# ind3v3.net
KiCad netlist of a schematic drawn in Altium Designer
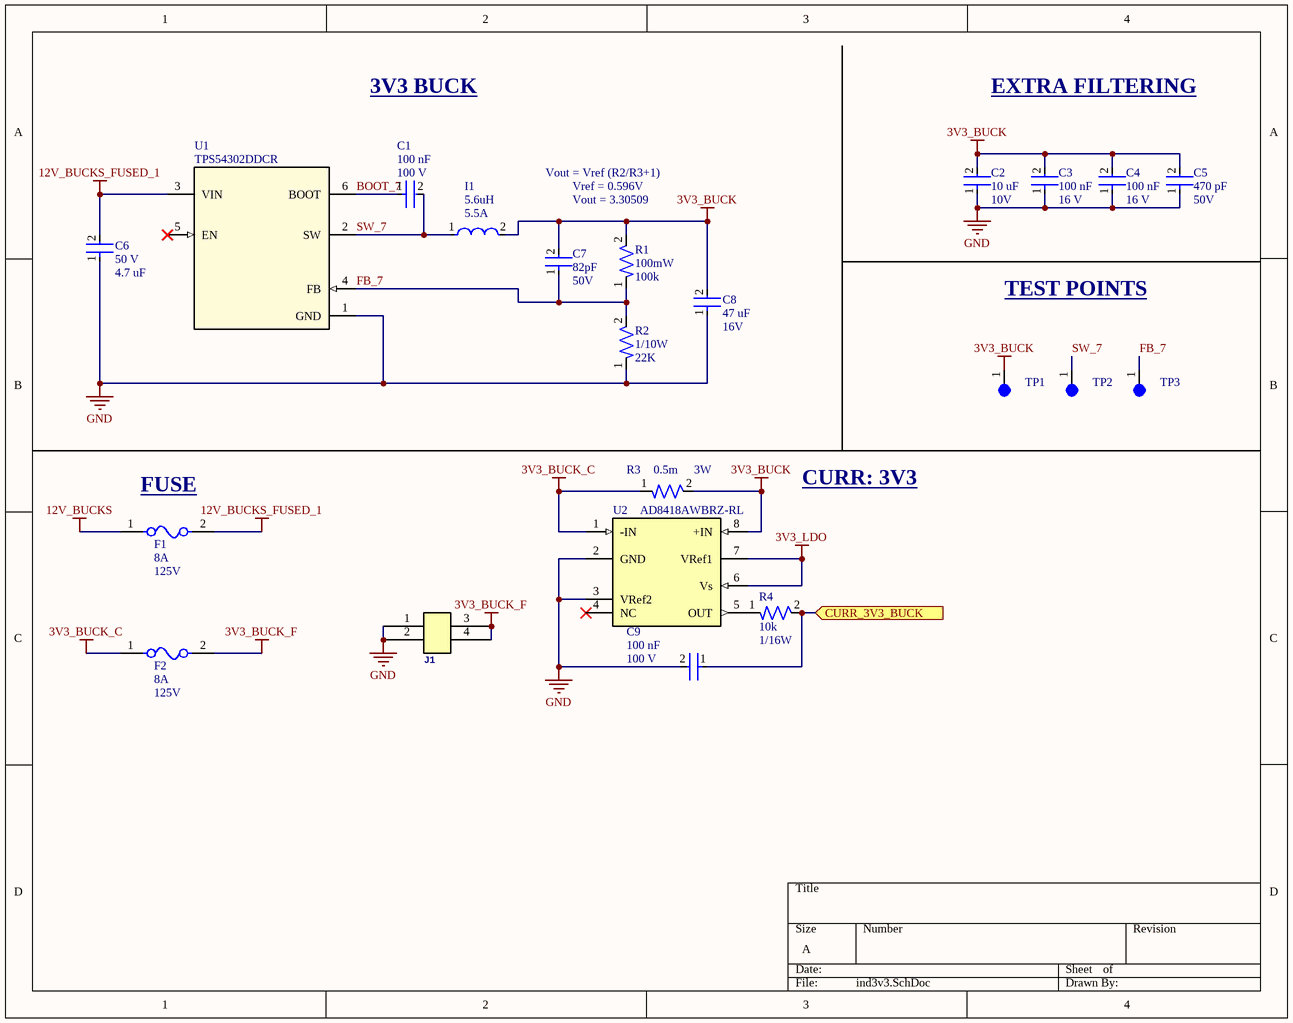
[diagram p0: ind3v3.SchDoc]

(export (version "E")
  (design (tool "Eeschema 10.0.6"))
  (components
    (comp (ref "C1")
      (value "CC0603KRX7R0BB104")
      (footprint "CAP-0603")
      (description "CAP CER 0.1UF 100V X7R 0603")
      (fields (field (name "CAPACITANCE") "100 nF") (field (name "VOLTAGE") "100 V"))
      (libsource (lib "JLC_25") (part "CAP-100N-0001"))
    )
    (comp (ref "C2")
      (value "CC0603KRX5R6BB106")
      (footprint "CAP-0603")
      (description "CAP CER 10UF 10V X5R 0603")
      (fields (field (name "VOLTAGE") "10V") (field (name "CAPACITANCE") "10 uF"))
      (libsource (lib "JLC_25") (part "CAP-10U-0001"))
    )
    (comp (ref "C3")
      (value "CC0402KRX7R7BB104")
      (footprint "CAP-0402")
      (description "CAP CER 0.1UF 16V X7R 0402")
      (fields (field (name "VOLTAGE RATING") "16 V") (field (name "CAPACITANCE") "100 nF"))
      (libsource (lib "JLC_25") (part "CAP-0.1U-0001"))
    )
    (comp (ref "C4")
      (value "CC0402KRX7R7BB104")
      (footprint "CAP-0402")
      (description "CAP CER 0.1UF 16V X7R 0402")
      (fields (field (name "VOLTAGE RATING") "16 V") (field (name "CAPACITANCE") "100 nF"))
      (libsource (lib "JLC_25") (part "CAP-0.1U-0001"))
    )
    (comp (ref "C5")
      (value "CC0805JRNPO9BN471")
      (footprint "CAP-0805")
      (description "CAP CER 470PF 50V C0G/NPO 0805")
      (fields (field (name "VOLTAGE") "50V") (field (name "CAPACITANCE") "470 pF"))
      (libsource (lib "JLC_25") (part "CAP-470P-0001"))
    )
    (comp (ref "C6")
      (value "CC0805KKX5R9BB475")
      (footprint "CAP-0805")
      (description "CAP CER 4.7UF 50V X5R 0805")
      (fields (field (name "VOLTAGE") "50 V") (field (name "CAPACITANCE") "4.7 uF"))
      (libsource (lib "JLC_25") (part "CAP-4.7U-0002"))
    )
    (comp (ref "C7")
      (value "CC0805JRNPO9BN820")
      (footprint "CAP-0805")
      (description "82 pF ±5% 50V Ceramic Capacitor C0G, NP0 0805 (2012 Metric)")
      (fields (field (name "VOLTAGE") "50V") (field (name "CAPACITANCE") "82pF"))
      (libsource (lib "JLC_25") (part "CAP-82P-0001"))
    )
    (comp (ref "C8")
      (value "GRM32ER61C476KE15L")
      (footprint "CAP-1210")
      (description "CAP CER 47UF 16V X5R 1210")
      (fields (field (name "CAPACITANCE") "47 uF") (field (name "VOLTAGE") "16V"))
      (libsource (lib "JLC_25") (part "CAP-47U-0002"))
    )
    (comp (ref "C9")
      (value "CC0603KRX7R0BB104")
      (footprint "CAP-0603")
      (description "CAP CER 0.1UF 100V X7R 0603")
      (fields (field (name "CAPACITANCE") "100 nF") (field (name "VOLTAGE") "100 V"))
      (libsource (lib "JLC_25") (part "CAP-100N-0001"))
    )
    (comp (ref "F1")
      (value "01550900M")
      (footprint "FUSE-0001")
      (description "FUSE BLOK CARTRIDGE 125V 10A SMD")
      (fields (field (name "FUSE CURRENT") "8A") (field (name "VOLTAGE RATING") "125V"))
      (libsource (lib "JLC_25") (part "FUSE-0001"))
    )
    (comp (ref "F2")
      (value "01550900M")
      (footprint "FUSE-0001")
      (description "FUSE BLOK CARTRIDGE 125V 10A SMD")
      (fields (field (name "FUSE CURRENT") "8A") (field (name "VOLTAGE RATING") "125V"))
      (libsource (lib "JLC_25") (part "FUSE-0001"))
    )
    (comp (ref "I1")
      (value "SRP6540-5R6M")
      (footprint "IND_SRP6540-5R6M")
      (description "FIXED IND 5.6UH 5.5A 38 MOHM SMD")
      (fields (field (name "SATURATION CURRENT") "5.5A") (field (name "INDUCTANCE") "5.6uH"))
      (libsource (lib "JLC_25") (part "IND-5.6U-0002"))
    )
    (comp (ref "J1")
      (value "Molex 43045-0412")
      (footprint "CONN-4POS-0002")
      (description "CONN HEADER VERT 4POS 3MM")
      (libsource (lib "JLC_25") (part "CONN-4POS-0002"))
    )
    (comp (ref "R1")
      (value "RC0603FR-07100KL")
      (footprint "RES-0603")
      (description "RES SMD 100K OHM 1% 1/10W 0603")
      (fields
        (field (name "TOLERANCE") "1%")
        (field (name "POWER") "100mW")
        (field (name "RESISTANCE") "100k")
      )
      (libsource (lib "JLC_25") (part "RES-100k-0001"))
    )
    (comp (ref "R2")
      (value "RC0603FR-0722KL")
      (footprint "RES-0603")
      (description "22 kOhms ±1% 0.1W, 1/10W Chip Resistor 0603 (1608 Metric) Moisture Resistant Thick Film")
      (fields (field (name "POWER") "1/10W") (field (name "RESISTANCE") "22K"))
      (libsource (lib "JLC_25") (part "RES-22k-0001"))
    )
    (comp (ref "R3")
      (value "CSNL2512FTL500")
      (footprint "RES-2512")
      (description "2512 Chip Resistor - Surface Mount ROHS")
      (fields (field (name "TOLERANCE") "1%") (field (name "POWER") "3W") (field (name "RESISTANCE") "0.5m"))
      (libsource (lib "JLC_25") (part "RES-0.5m-0001"))
    )
    (comp (ref "R4")
      (value "RC0402FR-0710KL")
      (footprint "RES-0402")
      (description "RES 10K OHM 1% 1/16W 0402")
      (fields
        (field (name "TOLERANCE") "1%")
        (field (name "RESISTANCE") "10k")
        (field (name "POWER") "1/16W")
      )
      (libsource (lib "JLC_25") (part "RES-10k-0001"))
    )
    (comp (ref "TP1")
      (value "5003")
      (footprint "TEST-POINT-0001")
      (description "Oranange PC Test Point, Miniature Phoisphor Bronze Silver Plating Through Hole Mounting Type")
      (libsource (lib "*") (part "TEST-POINT-0001"))
    )
    (comp (ref "TP2")
      (value "5003")
      (footprint "TEST-POINT-0001")
      (description "Oranange PC Test Point, Miniature Phoisphor Bronze Silver Plating Through Hole Mounting Type")
      (libsource (lib "*") (part "TEST-POINT-0001"))
    )
    (comp (ref "TP3")
      (value "5003")
      (footprint "TEST-POINT-0001")
      (description "Oranange PC Test Point, Miniature Phoisphor Bronze Silver Plating Through Hole Mounting Type")
      (libsource (lib "*") (part "TEST-POINT-0001"))
    )
    (comp (ref "U1")
      (value "TPS54302DDCR")
      (footprint "IC-SOT-23-6")
      (description "IC REG BUCK ADJ 3A SOT23")
      (libsource (lib "JLC_25") (part "IC-BUCK-0004"))
    )
    (comp (ref "U2")
      (value "AD8418AWBRZ-RL")
      (footprint "IC-CURR")
      (description "Current Sense Amplifier 1 Circuit 8-MSOP")
      (libsource (lib "JLC_25") (part "IC-CURR-0001"))
    )
  )
  (nets
    (net (code "1") (name "/BOOT_7") (class "Default")
      (node (ref "C1") (pin "1") (pinfunction "1_1") (pintype "passive"))
      (node (ref "U1") (pin "6") (pinfunction "BOOT_6") (pintype "power_in"))
    )
    (net (code "2") (name "/CURR_3V3_BUCK") (class "Default")
      (node (ref "C9") (pin "1") (pinfunction "1_1") (pintype "passive"))
      (node (ref "R4") (pin "2") (pinfunction "2_2") (pintype "passive"))
    )
    (net (code "3") (name "/FB_7") (class "Default")
      (node (ref "C7") (pin "1") (pinfunction "1_1") (pintype "passive"))
      (node (ref "R1") (pin "1") (pinfunction "1_1") (pintype "passive"))
      (node (ref "R2") (pin "2") (pinfunction "2_2") (pintype "passive"))
      (node (ref "TP3") (pin "1") (pinfunction "0_1") (pintype "passive"))
      (node (ref "U1") (pin "4") (pinfunction "FB_4") (pintype "input"))
    )
    (net (code "4") (name "/SW_7") (class "Default")
      (node (ref "C1") (pin "2") (pinfunction "2_2") (pintype "passive"))
      (node (ref "I1") (pin "1") (pinfunction "1_1") (pintype "passive"))
      (node (ref "TP2") (pin "1") (pinfunction "0_1") (pintype "passive"))
      (node (ref "U1") (pin "2") (pinfunction "SW_2") (pintype "power_in"))
    )
    (net (code "5") (name "3V3_BUCK") (class "Default")
      (node (ref "C2") (pin "2") (pinfunction "2_2") (pintype "passive"))
      (node (ref "C3") (pin "2") (pinfunction "2_2") (pintype "passive"))
      (node (ref "C4") (pin "2") (pinfunction "2_2") (pintype "passive"))
      (node (ref "C5") (pin "2") (pinfunction "2_2") (pintype "passive"))
      (node (ref "C7") (pin "2") (pinfunction "2_2") (pintype "passive"))
      (node (ref "C8") (pin "2") (pinfunction "2_2") (pintype "passive"))
      (node (ref "I1") (pin "2") (pinfunction "2_2") (pintype "passive"))
      (node (ref "R1") (pin "2") (pinfunction "2_2") (pintype "passive"))
      (node (ref "R3") (pin "2") (pinfunction "2_2") (pintype "passive"))
      (node (ref "TP1") (pin "1") (pinfunction "0_1") (pintype "passive"))
      (node (ref "U2") (pin "8") (pinfunction "+IN_8") (pintype "input"))
    )
    (net (code "6") (name "3V3_BUCK_C") (class "Default")
      (node (ref "F2") (pin "1") (pinfunction "1_1") (pintype "passive"))
      (node (ref "R3") (pin "1") (pinfunction "1_1") (pintype "passive"))
      (node (ref "U2") (pin "1") (pinfunction "-IN_1") (pintype "input"))
    )
    (net (code "7") (name "3V3_BUCK_F") (class "Default")
      (node (ref "F2") (pin "2") (pinfunction "2_2") (pintype "passive"))
      (node (ref "J1") (pin "3") (pinfunction "3_3") (pintype "passive"))
      (node (ref "J1") (pin "4") (pinfunction "4_4") (pintype "passive"))
    )
    (net (code "8") (name "3V3_LDO") (class "Default")
      (node (ref "U2") (pin "6") (pinfunction "Vs_6") (pintype "input"))
      (node (ref "U2") (pin "7") (pinfunction "VRef1_7") (pintype "power_in"))
    )
    (net (code "9") (name "12V_BUCKS") (class "Default")
      (node (ref "F1") (pin "1") (pinfunction "1_1") (pintype "passive"))
    )
    (net (code "10") (name "12V_BUCKS_FUSED_1") (class "Default")
      (node (ref "C6") (pin "2") (pinfunction "2_2") (pintype "passive"))
      (node (ref "F1") (pin "2") (pinfunction "2_2") (pintype "passive"))
      (node (ref "U1") (pin "3") (pinfunction "VIN_3") (pintype "power_in"))
    )
    (net (code "11") (name "GND") (class "Default")
      (node (ref "C2") (pin "1") (pinfunction "1_1") (pintype "passive"))
      (node (ref "C3") (pin "1") (pinfunction "1_1") (pintype "passive"))
      (node (ref "C4") (pin "1") (pinfunction "1_1") (pintype "passive"))
      (node (ref "C5") (pin "1") (pinfunction "1_1") (pintype "passive"))
      (node (ref "C6") (pin "1") (pinfunction "1_1") (pintype "passive"))
      (node (ref "C8") (pin "1") (pinfunction "1_1") (pintype "passive"))
      (node (ref "C9") (pin "2") (pinfunction "2_2") (pintype "passive"))
      (node (ref "J1") (pin "1") (pinfunction "1_1") (pintype "passive"))
      (node (ref "J1") (pin "2") (pinfunction "2_2") (pintype "passive"))
      (node (ref "R2") (pin "1") (pinfunction "1_1") (pintype "passive"))
      (node (ref "U1") (pin "1") (pinfunction "GND_1") (pintype "power_in"))
      (node (ref "U2") (pin "2") (pinfunction "GND_2") (pintype "power_in"))
      (node (ref "U2") (pin "3") (pinfunction "VRef2_3") (pintype "passive"))
    )
    (net (code "12") (name "Net-(U2-OUT)") (class "Default")
      (node (ref "R4") (pin "1") (pinfunction "1_1") (pintype "passive"))
      (node (ref "U2") (pin "5") (pinfunction "OUT_5") (pintype "output"))
    )
    (net (code "13") (name "unconnected-(U1-EN-Pad5)") (class "Default")
      (node (ref "U1") (pin "5") (pinfunction "EN_5") (pintype "input+no_connect"))
    )
    (net (code "14") (name "unconnected-(U2-NC-Pad4)") (class "Default")
      (node (ref "U2") (pin "4") (pinfunction "NC_4") (pintype "passive+no_connect"))
    )
  )
)
